# 9_-STM32F407_Controller.net
KiCad netlist of a schematic drawn in Altium Designer
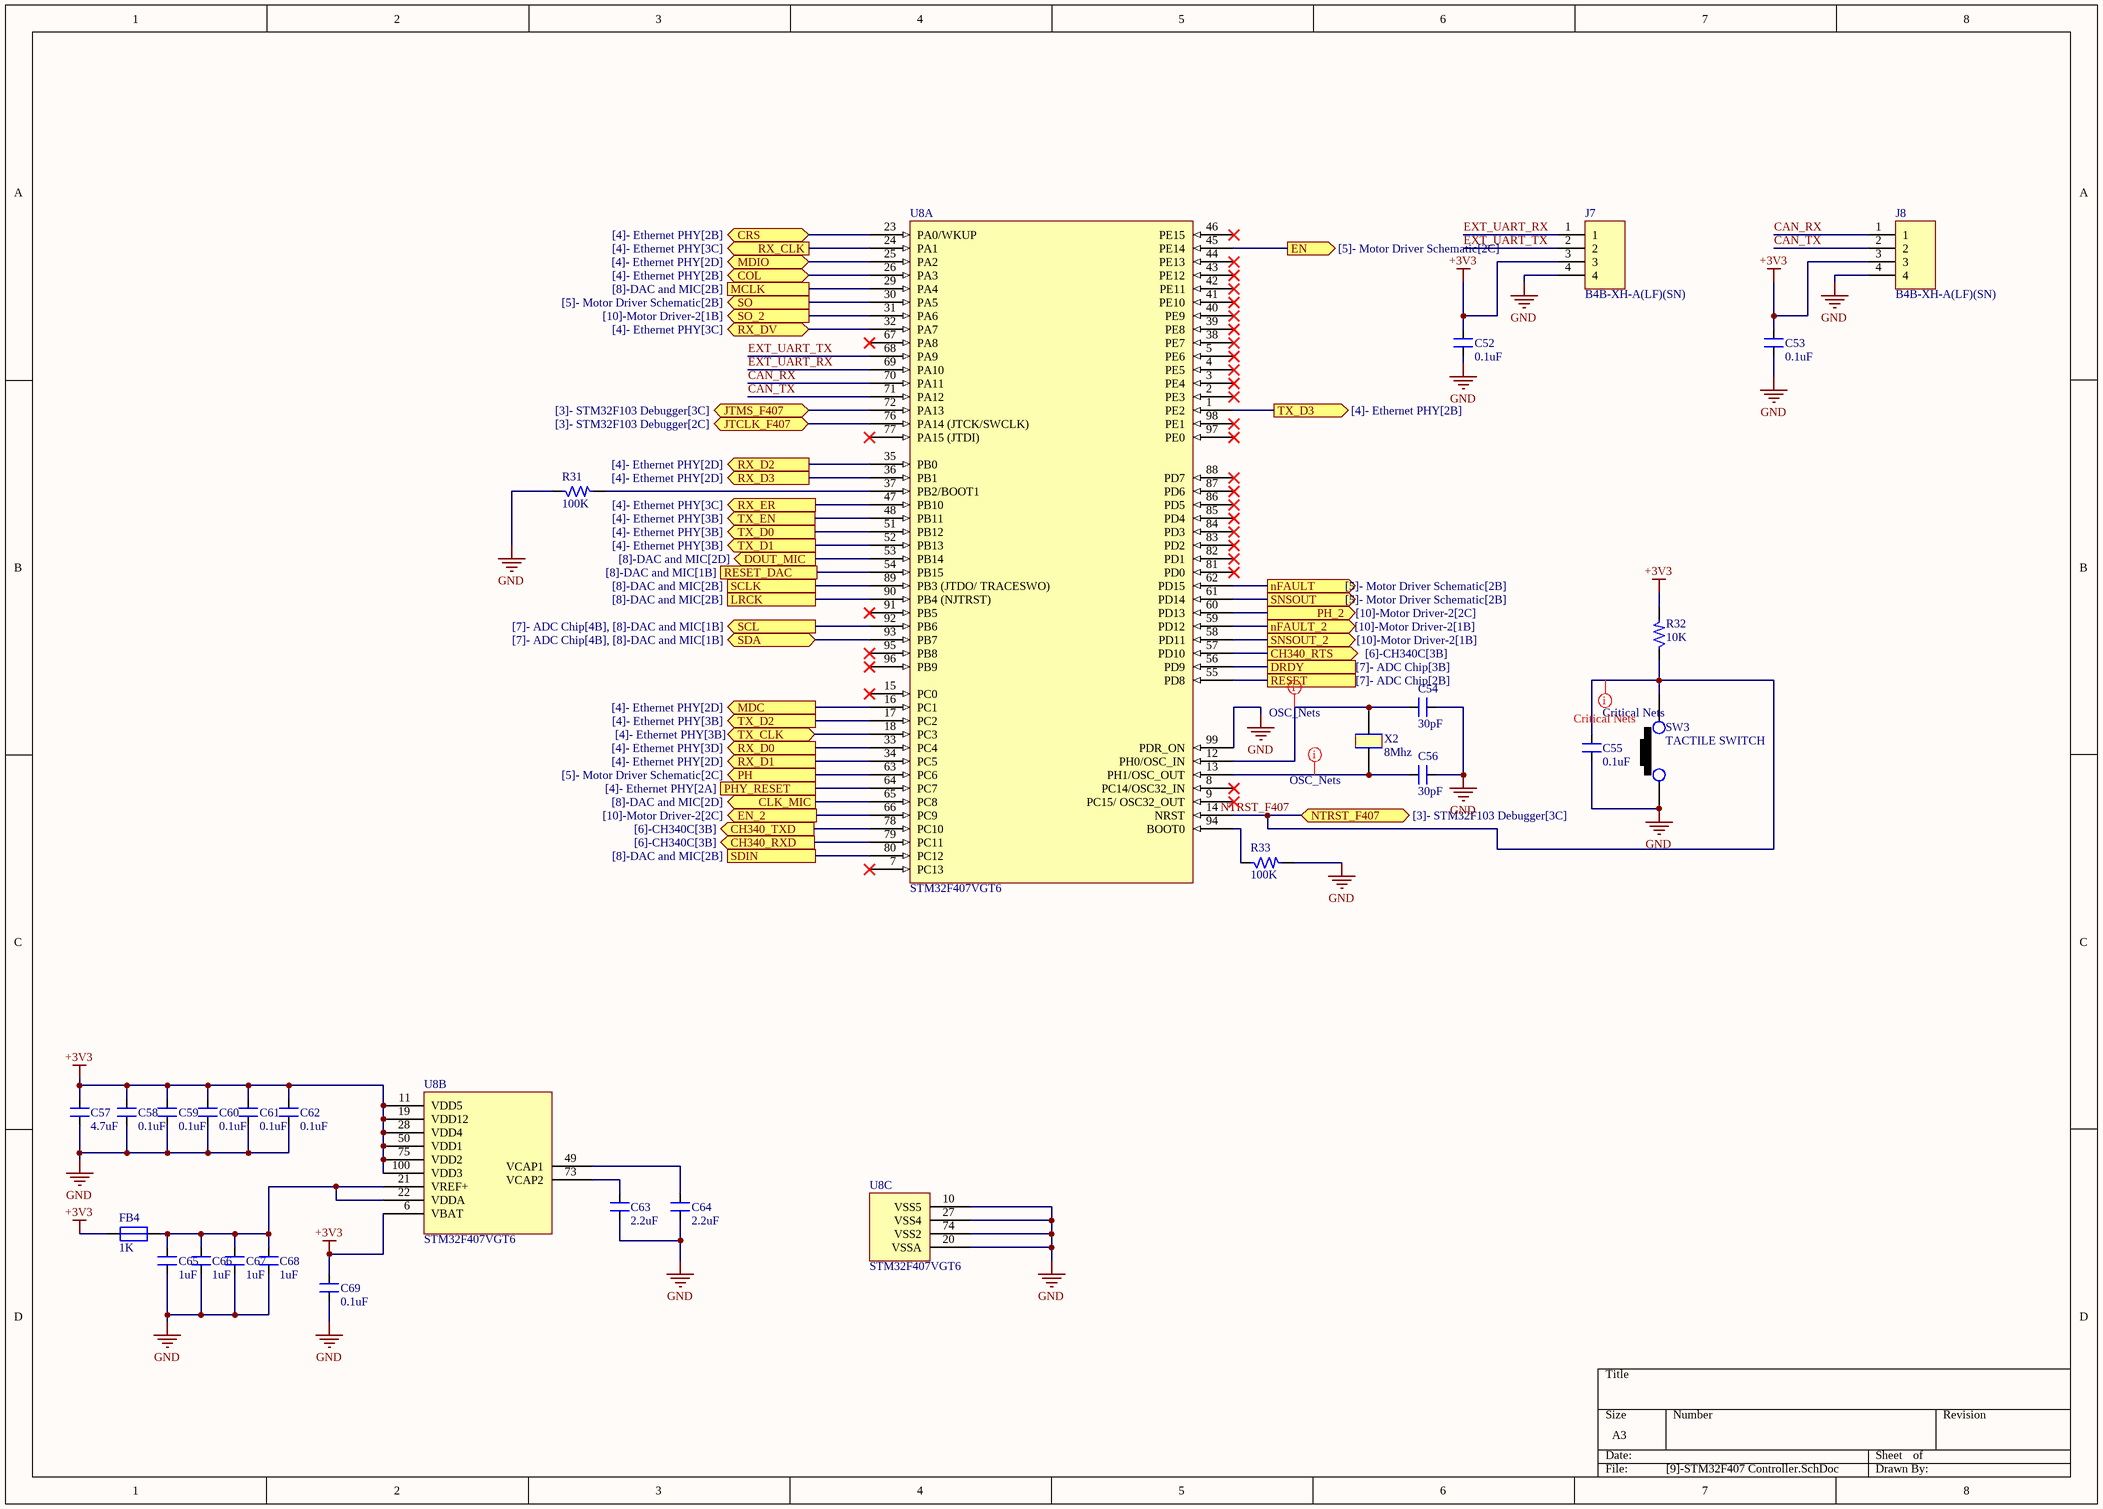
[diagram p0: [9]-STM32F407 Controller.SchDoc]

(export (version "E")
  (design (tool "Eeschema 10.0.6"))
  (components
    (comp (ref "C52")
      (value "0.1uF")
      (footprint "CAP_0805")
      (description "0.1µF ±10% 50V Ceramic Capacitor X7R 0805 (2012 Metric)")
      (fields
        (field (name "MANUFACTURER") "Samsung")
        (field (name "MANUFACTURER PART NUMBER") "CL21B104KBCNNNC")
      )
      (libsource (lib "ESTEEMPCBLIB") (part "CAP_0.1uF-50V-10%-0805"))
    )
    (comp (ref "C53")
      (value "0.1uF")
      (footprint "CAP_0805")
      (description "0.1µF ±10% 50V Ceramic Capacitor X7R 0805 (2012 Metric)")
      (fields
        (field (name "MANUFACTURER") "Samsung")
        (field (name "MANUFACTURER PART NUMBER") "CL21B104KBCNNNC")
      )
      (libsource (lib "ESTEEMPCBLIB") (part "CAP_0.1uF-50V-10%-0805"))
    )
    (comp (ref "C54")
      (value "30pF")
      (footprint "CAP_0805")
      (description "±10% 50V Ceramic Capacitor C0G, NP0 0805 (2012 Metric)")
      (fields
        (field (name "MANUFACTURER PART NUMBER") "C0805C300K5GAC7800")
        (field (name "MANUFACTURER") "KEMET")
      )
      (libsource (lib "ESTEEMPCBLIB") (part "CAP_30pF-50V-10%-0805"))
    )
    (comp (ref "C55")
      (value "0.1uF")
      (footprint "CAP_0805")
      (description "0.1µF ±10% 50V Ceramic Capacitor X7R 0805 (2012 Metric)")
      (fields
        (field (name "MANUFACTURER") "Samsung")
        (field (name "MANUFACTURER PART NUMBER") "CL21B104KBCNNNC")
      )
      (libsource (lib "ESTEEMPCBLIB") (part "CAP_0.1uF-50V-10%-0805"))
    )
    (comp (ref "C56")
      (value "30pF")
      (footprint "CAP_0805")
      (description "±10% 50V Ceramic Capacitor C0G, NP0 0805 (2012 Metric)")
      (fields
        (field (name "MANUFACTURER PART NUMBER") "C0805C300K5GAC7800")
        (field (name "MANUFACTURER") "KEMET")
      )
      (libsource (lib "ESTEEMPCBLIB") (part "CAP_30pF-50V-10%-0805"))
    )
    (comp (ref "C57")
      (value "4.7uF")
      (footprint "CAP_0805")
      (description "4.7µF ±10% 50V Ceramic Capacitor X5R 0805 (2012 Metric)")
      (fields
        (field (name "MANUFACTURER") "Yageo")
        (field (name "MANUFACTURER PART NUMBER") "GRM21BR61H475KE51L")
      )
      (libsource (lib "ESTEEMPCBLIB") (part "CAP_4.7uF-50V-10%-0805"))
    )
    (comp (ref "C58")
      (value "0.1uF")
      (footprint "CAP_0805")
      (description "0.1µF ±10% 50V Ceramic Capacitor X7R 0805 (2012 Metric)")
      (fields
        (field (name "MANUFACTURER") "Samsung")
        (field (name "MANUFACTURER PART NUMBER") "CL21B104KBCNNNC")
      )
      (libsource (lib "ESTEEMPCBLIB") (part "CAP_0.1uF-50V-10%-0805"))
    )
    (comp (ref "C59")
      (value "0.1uF")
      (footprint "CAP_0805")
      (description "0.1µF ±10% 50V Ceramic Capacitor X7R 0805 (2012 Metric)")
      (fields
        (field (name "MANUFACTURER") "Samsung")
        (field (name "MANUFACTURER PART NUMBER") "CL21B104KBCNNNC")
      )
      (libsource (lib "ESTEEMPCBLIB") (part "CAP_0.1uF-50V-10%-0805"))
    )
    (comp (ref "C60")
      (value "0.1uF")
      (footprint "CAP_0805")
      (description "0.1µF ±10% 50V Ceramic Capacitor X7R 0805 (2012 Metric)")
      (fields
        (field (name "MANUFACTURER") "Samsung")
        (field (name "MANUFACTURER PART NUMBER") "CL21B104KBCNNNC")
      )
      (libsource (lib "ESTEEMPCBLIB") (part "CAP_0.1uF-50V-10%-0805"))
    )
    (comp (ref "C61")
      (value "0.1uF")
      (footprint "CAP_0805")
      (description "0.1µF ±10% 50V Ceramic Capacitor X7R 0805 (2012 Metric)")
      (fields
        (field (name "MANUFACTURER") "Samsung")
        (field (name "MANUFACTURER PART NUMBER") "CL21B104KBCNNNC")
      )
      (libsource (lib "ESTEEMPCBLIB") (part "CAP_0.1uF-50V-10%-0805"))
    )
    (comp (ref "C62")
      (value "0.1uF")
      (footprint "CAP_0805")
      (description "0.1µF ±10% 50V Ceramic Capacitor X7R 0805 (2012 Metric)")
      (fields
        (field (name "MANUFACTURER") "Samsung")
        (field (name "MANUFACTURER PART NUMBER") "CL21B104KBCNNNC")
      )
      (libsource (lib "ESTEEMPCBLIB") (part "CAP_0.1uF-50V-10%-0805"))
    )
    (comp (ref "C63")
      (value "2.2uF")
      (footprint "CAP_0805")
      (description "2.2µF ±10% 25V Ceramic Capacitor X7R 0805 (2012 Metric)")
      (fields
        (field (name "MANUFACTURER") "KEMET")
        (field (name "MANUFACTURER PART NUMBER") "CL21B225KAFNFNE")
      )
      (libsource (lib "ESTEEMPCBLIB") (part "CAP_2.2uF-25V-10%-0805"))
    )
    (comp (ref "C64")
      (value "2.2uF")
      (footprint "CAP_0805")
      (description "2.2µF ±10% 25V Ceramic Capacitor X7R 0805 (2012 Metric)")
      (fields
        (field (name "MANUFACTURER") "KEMET")
        (field (name "MANUFACTURER PART NUMBER") "CL21B225KAFNFNE")
      )
      (libsource (lib "ESTEEMPCBLIB") (part "CAP_2.2uF-25V-10%-0805"))
    )
    (comp (ref "C65")
      (value "1uF")
      (footprint "CAP_0805")
      (description "1µF ±5% 50V Ceramic Capacitor X7R 0805 (2012 Metric)")
      (fields
        (field (name "MANUFACTURER") "Samsung")
        (field (name "MANUFACTURER PART NUMBER") "CC0805JKX7R9BB105")
      )
      (libsource (lib "ESTEEMPCBLIB") (part "CAP_1uF-50V-5%-0805"))
    )
    (comp (ref "C66")
      (value "1uF")
      (footprint "CAP_0805")
      (description "1µF ±5% 50V Ceramic Capacitor X7R 0805 (2012 Metric)")
      (fields
        (field (name "MANUFACTURER") "Samsung")
        (field (name "MANUFACTURER PART NUMBER") "CC0805JKX7R9BB105")
      )
      (libsource (lib "ESTEEMPCBLIB") (part "CAP_1uF-50V-5%-0805"))
    )
    (comp (ref "C67")
      (value "1uF")
      (footprint "CAP_0805")
      (description "1µF ±5% 50V Ceramic Capacitor X7R 0805 (2012 Metric)")
      (fields
        (field (name "MANUFACTURER") "Samsung")
        (field (name "MANUFACTURER PART NUMBER") "CC0805JKX7R9BB105")
      )
      (libsource (lib "ESTEEMPCBLIB") (part "CAP_1uF-50V-5%-0805"))
    )
    (comp (ref "C68")
      (value "1uF")
      (footprint "CAP_0805")
      (description "1µF ±5% 50V Ceramic Capacitor X7R 0805 (2012 Metric)")
      (fields
        (field (name "MANUFACTURER") "Samsung")
        (field (name "MANUFACTURER PART NUMBER") "CC0805JKX7R9BB105")
      )
      (libsource (lib "ESTEEMPCBLIB") (part "CAP_1uF-50V-5%-0805"))
    )
    (comp (ref "C69")
      (value "0.1uF")
      (footprint "CAP_0805")
      (description "0.1µF ±10% 50V Ceramic Capacitor X7R 0805 (2012 Metric)")
      (fields
        (field (name "MANUFACTURER") "Samsung")
        (field (name "MANUFACTURER PART NUMBER") "CL21B104KBCNNNC")
      )
      (libsource (lib "ESTEEMPCBLIB") (part "CAP_0.1uF-50V-10%-0805"))
    )
    (comp (ref "FB4")
      (value "1K")
      (footprint "IND_0805")
      (description "1 kOhms @ 100MHz 1 Power Line Ferrite Bead 0805 (2012 Metric) 1.6A")
      (fields
        (field (name "MANUFACTURER") "Laird")
        (field (name "MANUFACTURER PART NUMBER") "BLM21SP102SH1D")
      )
      (libsource (lib "ESTEEMPCBLIB") (part "FB_1K-100MHZ-1.6A-0805"))
    )
    (comp (ref "J7")
      (value "B4B-XH-A(LF)(SN)")
      (footprint "CON4_100_B4B-XH-A_TH_ST")
      (description "4 Pins, 1 Row 2.54mm Pitch, straight Connector, male")
      (fields (field (name "MANUFACTURER") "Wurth Electronics") (field (name "MATING PART NUMBER") "XHP-4"))
      (libsource (lib "ESTEEMPCBLIB") (part "CON-PLG_4X1-100-ST-TH"))
    )
    (comp (ref "J8")
      (value "B4B-XH-A(LF)(SN)")
      (footprint "CON4_100_B4B-XH-A_TH_ST")
      (description "4 Pins, 1 Row 2.54mm Pitch, straight Connector, male")
      (fields (field (name "MANUFACTURER") "Wurth Electronics") (field (name "MATING PART NUMBER") "XHP-4"))
      (libsource (lib "ESTEEMPCBLIB") (part "CON-PLG_4X1-100-ST-TH"))
    )
    (comp (ref "R31")
      (value "100K")
      (footprint "RES_0603")
      (description "100 kOhms ±1% 0.1W, 1/10W Chip Resistor 0603 (1608 Metric) Automotive AEC-Q200 Thick Film")
      (fields
        (field (name "MANUFACTURER") "Stackpole Electronics")
        (field (name "MANUFACTURER PART NUMBER") "RMCF0603FT100K")
      )
      (libsource (lib "ESTEEMPCBLIB") (part "RES_100K-0.1W-1%-0603"))
    )
    (comp (ref "R32")
      (value "10K")
      (footprint "RES_0603")
      (description "10 kOhms ±1% 0.1W, 1/10W Chip Resistor 0603 (1608 Metric) Automotive AEC-Q200 Thick Film")
      (fields (field (name "MANUFACTURER") "Walsin") (field (name "MANUFACTURER PART NUMBER") "WR06X1002FTL"))
      (libsource (lib "ESTEEMPCBLIB") (part "RES_10K-0.1W-1%-0603"))
    )
    (comp (ref "R33")
      (value "100K")
      (footprint "RES_0603")
      (description "100 kOhms ±1% 0.1W, 1/10W Chip Resistor 0603 (1608 Metric) Automotive AEC-Q200 Thick Film")
      (fields
        (field (name "MANUFACTURER") "Stackpole Electronics")
        (field (name "MANUFACTURER PART NUMBER") "RMCF0603FT100K")
      )
      (libsource (lib "ESTEEMPCBLIB") (part "RES_100K-0.1W-1%-0603"))
    )
    (comp (ref "SW3")
      (value "TACTILE SWITCH")
      (footprint "SW_342_SMD")
      (description "Tactile Switch SPST-NO Top Actuated Surface Mount")
      (fields
        (field (name "MANUFACTURER") "ITT C&K")
        (field (name "MANUFACTURER PART NUMBER") "RS-282G05A3-SMRT")
      )
      (libsource (lib "ESTEEMPCBLIB") (part "SW1_RS-282G05A3-SMRT-SMD"))
    )
    (comp (ref "U8")
      (value "STM32F407VGT6")
      (footprint "QFN100_19.6_669_58X10_SMD")
      (description "ARM® Cortex®-M4 STM32F4 Microcontroller IC 32-Bit 168MHz 1MB (1M x 8) FLASH 100-LQFP (14x14)")
      (fields (field (name "MANUFACTURER") "STMicroelectronics"))
      (libsource (lib "ESTEEMPCBLIB") (part "IC_STM32F407VGT6"))
    )
    (comp (ref "X2")
      (value "8Mhz")
      (footprint "XTAL_314_240X47_SMD")
      (description "8MHz ±30ppm Crystal 32pF 60 Ohms HC-49/US")
      (fields
        (field (name "MANUFACTURER") "Fox Electronics")
        (field (name "MANUFACTURER PART NUMBER") "ECS-80-32-5PX-TR")
      )
      (libsource (lib "ESTEEMPCBLIB") (part "XTAL_8MHZ-ECS-80-32-5PX-SMD"))
    )
  )
  (nets
    (net (code "1") (name "+3V3") (class "Default")
      (node (ref "C52") (pin "2") (pinfunction "2_2") (pintype "passive"))
      (node (ref "C53") (pin "2") (pinfunction "2_2") (pintype "passive"))
      (node (ref "C57") (pin "2") (pinfunction "2_2") (pintype "passive"))
      (node (ref "C58") (pin "2") (pinfunction "2_2") (pintype "passive"))
      (node (ref "C59") (pin "2") (pinfunction "2_2") (pintype "passive"))
      (node (ref "C60") (pin "2") (pinfunction "2_2") (pintype "passive"))
      (node (ref "C61") (pin "2") (pinfunction "2_2") (pintype "passive"))
      (node (ref "C62") (pin "2") (pinfunction "2_2") (pintype "passive"))
      (node (ref "C69") (pin "1") (pinfunction "1_1") (pintype "passive"))
      (node (ref "FB4") (pin "1") (pinfunction "1_1") (pintype "passive"))
      (node (ref "J7") (pin "3") (pinfunction "3_3") (pintype "passive"))
      (node (ref "J8") (pin "3") (pinfunction "3_3") (pintype "passive"))
      (node (ref "R32") (pin "2") (pinfunction "2_2") (pintype "passive"))
      (node (ref "U8") (pin "100") (pinfunction "VDD3_100") (pintype "passive"))
      (node (ref "U8") (pin "11") (pinfunction "VDD5_11") (pintype "passive"))
      (node (ref "U8") (pin "19") (pinfunction "VDD12_19") (pintype "passive"))
      (node (ref "U8") (pin "28") (pinfunction "VDD4_28") (pintype "passive"))
      (node (ref "U8") (pin "50") (pinfunction "VDD1_50") (pintype "passive"))
      (node (ref "U8") (pin "6") (pinfunction "VBAT_6") (pintype "passive"))
      (node (ref "U8") (pin "75") (pinfunction "VDD2_75") (pintype "passive"))
    )
    (net (code "2") (name "/CAN_RX") (class "Default")
      (node (ref "J8") (pin "1") (pinfunction "1_1") (pintype "passive"))
      (node (ref "U8") (pin "70") (pinfunction "PA11_70") (pintype "input"))
    )
    (net (code "3") (name "/CAN_TX") (class "Default")
      (node (ref "J8") (pin "2") (pinfunction "2_2") (pintype "passive"))
      (node (ref "U8") (pin "71") (pinfunction "PA12_71") (pintype "input"))
    )
    (net (code "4") (name "/CH340_RTS") (class "Default")
      (node (ref "U8") (pin "57") (pinfunction "PD10_57") (pintype "input"))
    )
    (net (code "5") (name "/CH340_RXD") (class "Default")
      (node (ref "U8") (pin "79") (pinfunction "PC11_79") (pintype "input"))
    )
    (net (code "6") (name "/CH340_TXD") (class "Default")
      (node (ref "U8") (pin "78") (pinfunction "PC10_78") (pintype "input"))
    )
    (net (code "7") (name "/CLK_MIC") (class "Default")
      (node (ref "U8") (pin "65") (pinfunction "PC8_65") (pintype "input"))
    )
    (net (code "8") (name "/COL") (class "Default")
      (node (ref "U8") (pin "26") (pinfunction "PA3_26") (pintype "input"))
    )
    (net (code "9") (name "/CRS") (class "Default")
      (node (ref "U8") (pin "23") (pinfunction "PA0/WKUP_23") (pintype "input"))
    )
    (net (code "10") (name "/DOUT_MIC") (class "Default")
      (node (ref "U8") (pin "53") (pinfunction "PB14_53") (pintype "input"))
    )
    (net (code "11") (name "/DRDY") (class "Default")
      (node (ref "U8") (pin "56") (pinfunction "PD9_56") (pintype "input"))
    )
    (net (code "12") (name "/EN") (class "Default")
      (node (ref "U8") (pin "45") (pinfunction "PE14_45") (pintype "input"))
    )
    (net (code "13") (name "/EN_2") (class "Default")
      (node (ref "U8") (pin "66") (pinfunction "PC9_66") (pintype "input"))
    )
    (net (code "14") (name "/EXT_UART_RX") (class "Default")
      (node (ref "J7") (pin "1") (pinfunction "1_1") (pintype "passive"))
      (node (ref "U8") (pin "69") (pinfunction "PA10_69") (pintype "input"))
    )
    (net (code "15") (name "/EXT_UART_TX") (class "Default")
      (node (ref "J7") (pin "2") (pinfunction "2_2") (pintype "passive"))
      (node (ref "U8") (pin "68") (pinfunction "PA9_68") (pintype "input"))
    )
    (net (code "16") (name "/JTCLK_F407") (class "Default")
      (node (ref "U8") (pin "76") (pinfunction "PA14_(JTCK/SWCLK)_76") (pintype "input"))
    )
    (net (code "17") (name "/JTMS_F407") (class "Default")
      (node (ref "U8") (pin "72") (pinfunction "PA13_72") (pintype "input"))
    )
    (net (code "18") (name "/LRCK") (class "Default")
      (node (ref "U8") (pin "90") (pinfunction "PB4_(NJTRST)_90") (pintype "input"))
    )
    (net (code "19") (name "/MCLK") (class "Default")
      (node (ref "U8") (pin "29") (pinfunction "PA4_29") (pintype "input"))
    )
    (net (code "20") (name "/MDC") (class "Default")
      (node (ref "U8") (pin "16") (pinfunction "PC1_16") (pintype "input"))
    )
    (net (code "21") (name "/MDIO") (class "Default")
      (node (ref "U8") (pin "25") (pinfunction "PA2_25") (pintype "input"))
    )
    (net (code "22") (name "/NTRST_F407") (class "Default")
      (node (ref "C55") (pin "2") (pinfunction "2_2") (pintype "passive"))
      (node (ref "R32") (pin "1") (pinfunction "1_1") (pintype "passive"))
      (node (ref "SW3") (pin "2") (pinfunction "2_2") (pintype "passive"))
      (node (ref "U8") (pin "14") (pinfunction "NRST_14") (pintype "input"))
    )
    (net (code "23") (name "/PH") (class "Default")
      (node (ref "U8") (pin "63") (pinfunction "PC6_63") (pintype "input"))
    )
    (net (code "24") (name "/PHY_RESET") (class "Default")
      (node (ref "U8") (pin "64") (pinfunction "PC7_64") (pintype "input"))
    )
    (net (code "25") (name "/PH_2") (class "Default")
      (node (ref "U8") (pin "60") (pinfunction "PD13_60") (pintype "input"))
    )
    (net (code "26") (name "/RESET") (class "Default")
      (node (ref "U8") (pin "55") (pinfunction "PD8_55") (pintype "input"))
    )
    (net (code "27") (name "/RESET_DAC") (class "Default")
      (node (ref "U8") (pin "54") (pinfunction "PB15_54") (pintype "input"))
    )
    (net (code "28") (name "/RX_CLK") (class "Default")
      (node (ref "U8") (pin "24") (pinfunction "PA1_24") (pintype "input"))
    )
    (net (code "29") (name "/RX_D0") (class "Default")
      (node (ref "U8") (pin "33") (pinfunction "PC4_33") (pintype "input"))
    )
    (net (code "30") (name "/RX_D1") (class "Default")
      (node (ref "U8") (pin "34") (pinfunction "PC5_34") (pintype "input"))
    )
    (net (code "31") (name "/RX_D2") (class "Default")
      (node (ref "U8") (pin "35") (pinfunction "PB0_35") (pintype "input"))
    )
    (net (code "32") (name "/RX_D3") (class "Default")
      (node (ref "U8") (pin "36") (pinfunction "PB1_36") (pintype "input"))
    )
    (net (code "33") (name "/RX_DV") (class "Default")
      (node (ref "U8") (pin "32") (pinfunction "PA7_32") (pintype "input"))
    )
    (net (code "34") (name "/RX_ER") (class "Default")
      (node (ref "U8") (pin "47") (pinfunction "PB10_47") (pintype "input"))
    )
    (net (code "35") (name "/SCL") (class "Default")
      (node (ref "U8") (pin "92") (pinfunction "PB6_92") (pintype "input"))
    )
    (net (code "36") (name "/SCLK") (class "Default")
      (node (ref "U8") (pin "89") (pinfunction "PB3_(JTDO/_TRACESWO)_89") (pintype "input"))
    )
    (net (code "37") (name "/SDA") (class "Default")
      (node (ref "U8") (pin "93") (pinfunction "PB7_93") (pintype "input"))
    )
    (net (code "38") (name "/SDIN") (class "Default")
      (node (ref "U8") (pin "80") (pinfunction "PC12_80") (pintype "input"))
    )
    (net (code "39") (name "/SNSOUT") (class "Default")
      (node (ref "U8") (pin "61") (pinfunction "PD14_61") (pintype "input"))
    )
    (net (code "40") (name "/SNSOUT_2") (class "Default")
      (node (ref "U8") (pin "58") (pinfunction "PD11_58") (pintype "input"))
    )
    (net (code "41") (name "/SO") (class "Default")
      (node (ref "U8") (pin "30") (pinfunction "PA5_30") (pintype "input"))
    )
    (net (code "42") (name "/SO_2") (class "Default")
      (node (ref "U8") (pin "31") (pinfunction "PA6_31") (pintype "input"))
    )
    (net (code "43") (name "/TX_CLK") (class "Default")
      (node (ref "U8") (pin "18") (pinfunction "PC3_18") (pintype "input"))
    )
    (net (code "44") (name "/TX_D0") (class "Default")
      (node (ref "U8") (pin "51") (pinfunction "PB12_51") (pintype "input"))
    )
    (net (code "45") (name "/TX_D1") (class "Default")
      (node (ref "U8") (pin "52") (pinfunction "PB13_52") (pintype "input"))
    )
    (net (code "46") (name "/TX_D2") (class "Default")
      (node (ref "U8") (pin "17") (pinfunction "PC2_17") (pintype "input"))
    )
    (net (code "47") (name "/TX_D3") (class "Default")
      (node (ref "U8") (pin "1") (pinfunction "PE2_1") (pintype "input"))
    )
    (net (code "48") (name "/TX_EN") (class "Default")
      (node (ref "U8") (pin "48") (pinfunction "PB11_48") (pintype "input"))
    )
    (net (code "49") (name "/nFAULT") (class "Default")
      (node (ref "U8") (pin "62") (pinfunction "PD15_62") (pintype "input"))
    )
    (net (code "50") (name "/nFAULT_2") (class "Default")
      (node (ref "U8") (pin "59") (pinfunction "PD12_59") (pintype "input"))
    )
    (net (code "51") (name "GND") (class "Default")
      (node (ref "C52") (pin "1") (pinfunction "1_1") (pintype "passive"))
      (node (ref "C53") (pin "1") (pinfunction "1_1") (pintype "passive"))
      (node (ref "C54") (pin "2") (pinfunction "2_2") (pintype "passive"))
      (node (ref "C55") (pin "1") (pinfunction "1_1") (pintype "passive"))
      (node (ref "C56") (pin "2") (pinfunction "2_2") (pintype "passive"))
      (node (ref "C57") (pin "1") (pinfunction "1_1") (pintype "passive"))
      (node (ref "C58") (pin "1") (pinfunction "1_1") (pintype "passive"))
      (node (ref "C59") (pin "1") (pinfunction "1_1") (pintype "passive"))
      (node (ref "C60") (pin "1") (pinfunction "1_1") (pintype "passive"))
      (node (ref "C61") (pin "1") (pinfunction "1_1") (pintype "passive"))
      (node (ref "C62") (pin "1") (pinfunction "1_1") (pintype "passive"))
      (node (ref "C63") (pin "1") (pinfunction "1_1") (pintype "passive"))
      (node (ref "C64") (pin "1") (pinfunction "1_1") (pintype "passive"))
      (node (ref "C65") (pin "1") (pinfunction "1_1") (pintype "passive"))
      (node (ref "C66") (pin "1") (pinfunction "1_1") (pintype "passive"))
      (node (ref "C67") (pin "1") (pinfunction "1_1") (pintype "passive"))
      (node (ref "C68") (pin "1") (pinfunction "1_1") (pintype "passive"))
      (node (ref "C69") (pin "2") (pinfunction "2_2") (pintype "passive"))
      (node (ref "J7") (pin "4") (pinfunction "4_4") (pintype "passive"))
      (node (ref "J8") (pin "4") (pinfunction "4_4") (pintype "passive"))
      (node (ref "R31") (pin "1") (pinfunction "1_1") (pintype "passive"))
      (node (ref "R33") (pin "2") (pinfunction "2_2") (pintype "passive"))
      (node (ref "SW3") (pin "1") (pinfunction "1_1") (pintype "passive"))
      (node (ref "U8") (pin "10") (pinfunction "VSS5_10") (pintype "passive"))
      (node (ref "U8") (pin "20") (pinfunction "VSSA_20") (pintype "passive"))
      (node (ref "U8") (pin "27") (pinfunction "VSS4_27") (pintype "passive"))
      (node (ref "U8") (pin "74") (pinfunction "VSS2_74") (pintype "passive"))
      (node (ref "U8") (pin "99") (pinfunction "PDR_ON_99") (pintype "input"))
    )
    (net (code "52") (name "Net-(U8A-BOOT0)") (class "Default")
      (node (ref "R33") (pin "1") (pinfunction "1_1") (pintype "passive"))
      (node (ref "U8") (pin "94") (pinfunction "BOOT0_94") (pintype "input"))
    )
    (net (code "53") (name "Net-(U8A-PB2{slash}BOOT1)") (class "Default")
      (node (ref "R31") (pin "2") (pinfunction "2_2") (pintype "passive"))
      (node (ref "U8") (pin "37") (pinfunction "PB2/BOOT1_37") (pintype "input"))
    )
    (net (code "54") (name "Net-(U8A-PH0{slash}OSC_IN)") (class "Default")
      (node (ref "C54") (pin "1") (pinfunction "1_1") (pintype "passive"))
      (node (ref "U8") (pin "12") (pinfunction "PH0/OSC_IN_12") (pintype "input"))
      (node (ref "X2") (pin "2") (pinfunction "2_2") (pintype "passive"))
    )
    (net (code "55") (name "Net-(U8A-PH1{slash}OSC_OUT)") (class "Default")
      (node (ref "C56") (pin "1") (pinfunction "1_1") (pintype "passive"))
      (node (ref "U8") (pin "13") (pinfunction "PH1/OSC_OUT_13") (pintype "input"))
      (node (ref "X2") (pin "1") (pinfunction "1_1") (pintype "passive"))
    )
    (net (code "56") (name "Net-(U8B-VCAP1)") (class "Default")
      (node (ref "C64") (pin "2") (pinfunction "2_2") (pintype "passive"))
      (node (ref "U8") (pin "49") (pinfunction "VCAP1_49") (pintype "passive"))
    )
    (net (code "57") (name "Net-(U8B-VCAP2)") (class "Default")
      (node (ref "C63") (pin "2") (pinfunction "2_2") (pintype "passive"))
      (node (ref "U8") (pin "73") (pinfunction "VCAP2_73") (pintype "passive"))
    )
    (net (code "58") (name "Net-(U8B-VDDA)") (class "Default")
      (node (ref "C65") (pin "2") (pinfunction "2_2") (pintype "passive"))
      (node (ref "C66") (pin "2") (pinfunction "2_2") (pintype "passive"))
      (node (ref "C67") (pin "2") (pinfunction "2_2") (pintype "passive"))
      (node (ref "C68") (pin "2") (pinfunction "2_2") (pintype "passive"))
      (node (ref "FB4") (pin "2") (pinfunction "2_2") (pintype "passive"))
      (node (ref "U8") (pin "21") (pinfunction "VREF+_21") (pintype "passive"))
      (node (ref "U8") (pin "22") (pinfunction "VDDA_22") (pintype "passive"))
    )
    (net (code "59") (name "unconnected-(U8A-PA8-Pad67)") (class "Default")
      (node (ref "U8") (pin "67") (pinfunction "PA8_67") (pintype "input+no_connect"))
    )
    (net (code "60") (name "unconnected-(U8A-PA15_(JTDI)-Pad77)") (class "Default")
      (node (ref "U8") (pin "77") (pinfunction "PA15_(JTDI)_77") (pintype "input+no_connect"))
    )
    (net (code "61") (name "unconnected-(U8A-PB5-Pad91)") (class "Default")
      (node (ref "U8") (pin "91") (pinfunction "PB5_91") (pintype "input+no_connect"))
    )
    (net (code "62") (name "unconnected-(U8A-PB8-Pad95)") (class "Default")
      (node (ref "U8") (pin "95") (pinfunction "PB8_95") (pintype "input+no_connect"))
    )
    (net (code "63") (name "unconnected-(U8A-PB9-Pad96)") (class "Default")
      (node (ref "U8") (pin "96") (pinfunction "PB9_96") (pintype "input+no_connect"))
    )
    (net (code "64") (name "unconnected-(U8A-PC0-Pad15)") (class "Default")
      (node (ref "U8") (pin "15") (pinfunction "PC0_15") (pintype "input+no_connect"))
    )
    (net (code "65") (name "unconnected-(U8A-PC13-Pad7)") (class "Default")
      (node (ref "U8") (pin "7") (pinfunction "PC13_7") (pintype "input+no_connect"))
    )
    (net (code "66") (name "unconnected-(U8A-PC14{slash}OSC32_IN-Pad8)") (class "Default")
      (node (ref "U8") (pin "8") (pinfunction "PC14/OSC32_IN_8") (pintype "input+no_connect"))
    )
    (net (code "67") (name "unconnected-(U8A-PC15{slash}_OSC32_OUT-Pad9)") (class "Default")
      (node (ref "U8") (pin "9") (pinfunction "PC15/_OSC32_OUT_9") (pintype "input+no_connect"))
    )
    (net (code "68") (name "unconnected-(U8A-PD0-Pad81)") (class "Default")
      (node (ref "U8") (pin "81") (pinfunction "PD0_81") (pintype "input+no_connect"))
    )
    (net (code "69") (name "unconnected-(U8A-PD1-Pad82)") (class "Default")
      (node (ref "U8") (pin "82") (pinfunction "PD1_82") (pintype "input+no_connect"))
    )
    (net (code "70") (name "unconnected-(U8A-PD2-Pad83)") (class "Default")
      (node (ref "U8") (pin "83") (pinfunction "PD2_83") (pintype "input+no_connect"))
    )
    (net (code "71") (name "unconnected-(U8A-PD3-Pad84)") (class "Default")
      (node (ref "U8") (pin "84") (pinfunction "PD3_84") (pintype "input+no_connect"))
    )
    (net (code "72") (name "unconnected-(U8A-PD4-Pad85)") (class "Default")
      (node (ref "U8") (pin "85") (pinfunction "PD4_85") (pintype "input+no_connect"))
    )
    (net (code "73") (name "unconnected-(U8A-PD5-Pad86)") (class "Default")
      (node (ref "U8") (pin "86") (pinfunction "PD5_86") (pintype "input+no_connect"))
    )
    (net (code "74") (name "unconnected-(U8A-PD6-Pad87)") (class "Default")
      (node (ref "U8") (pin "87") (pinfunction "PD6_87") (pintype "input+no_connect"))
    )
    (net (code "75") (name "unconnected-(U8A-PD7-Pad88)") (class "Default")
      (node (ref "U8") (pin "88") (pinfunction "PD7_88") (pintype "input+no_connect"))
    )
    (net (code "76") (name "unconnected-(U8A-PE0-Pad97)") (class "Default")
      (node (ref "U8") (pin "97") (pinfunction "PE0_97") (pintype "input+no_connect"))
    )
    (net (code "77") (name "unconnected-(U8A-PE1-Pad98)") (class "Default")
      (node (ref "U8") (pin "98") (pinfunction "PE1_98") (pintype "input+no_connect"))
    )
    (net (code "78") (name "unconnected-(U8A-PE3-Pad2)") (class "Default")
      (node (ref "U8") (pin "2") (pinfunction "PE3_2") (pintype "input+no_connect"))
    )
    (net (code "79") (name "unconnected-(U8A-PE4-Pad3)") (class "Default")
      (node (ref "U8") (pin "3") (pinfunction "PE4_3") (pintype "input+no_connect"))
    )
    (net (code "80") (name "unconnected-(U8A-PE5-Pad4)") (class "Default")
      (node (ref "U8") (pin "4") (pinfunction "PE5_4") (pintype "input+no_connect"))
    )
    (net (code "81") (name "unconnected-(U8A-PE6-Pad5)") (class "Default")
      (node (ref "U8") (pin "5") (pinfunction "PE6_5") (pintype "input+no_connect"))
    )
    (net (code "82") (name "unconnected-(U8A-PE7-Pad38)") (class "Default")
      (node (ref "U8") (pin "38") (pinfunction "PE7_38") (pintype "input+no_connect"))
    )
    (net (code "83") (name "unconnected-(U8A-PE8-Pad39)") (class "Default")
      (node (ref "U8") (pin "39") (pinfunction "PE8_39") (pintype "input+no_connect"))
    )
    (net (code "84") (name "unconnected-(U8A-PE9-Pad40)") (class "Default")
      (node (ref "U8") (pin "40") (pinfunction "PE9_40") (pintype "input+no_connect"))
    )
    (net (code "85") (name "unconnected-(U8A-PE10-Pad41)") (class "Default")
      (node (ref "U8") (pin "41") (pinfunction "PE10_41") (pintype "input+no_connect"))
    )
    (net (code "86") (name "unconnected-(U8A-PE11-Pad42)") (class "Default")
      (node (ref "U8") (pin "42") (pinfunction "PE11_42") (pintype "input+no_connect"))
    )
    (net (code "87") (name "unconnected-(U8A-PE12-Pad43)") (class "Default")
      (node (ref "U8") (pin "43") (pinfunction "PE12_43") (pintype "input+no_connect"))
    )
    (net (code "88") (name "unconnected-(U8A-PE13-Pad44)") (class "Default")
      (node (ref "U8") (pin "44") (pinfunction "PE13_44") (pintype "input+no_connect"))
    )
    (net (code "89") (name "unconnected-(U8A-PE15-Pad46)") (class "Default")
      (node (ref "U8") (pin "46") (pinfunction "PE15_46") (pintype "input+no_connect"))
    )
  )
)
